# PIC32ETH.net
KiCad netlist of a schematic drawn in Altium Designer
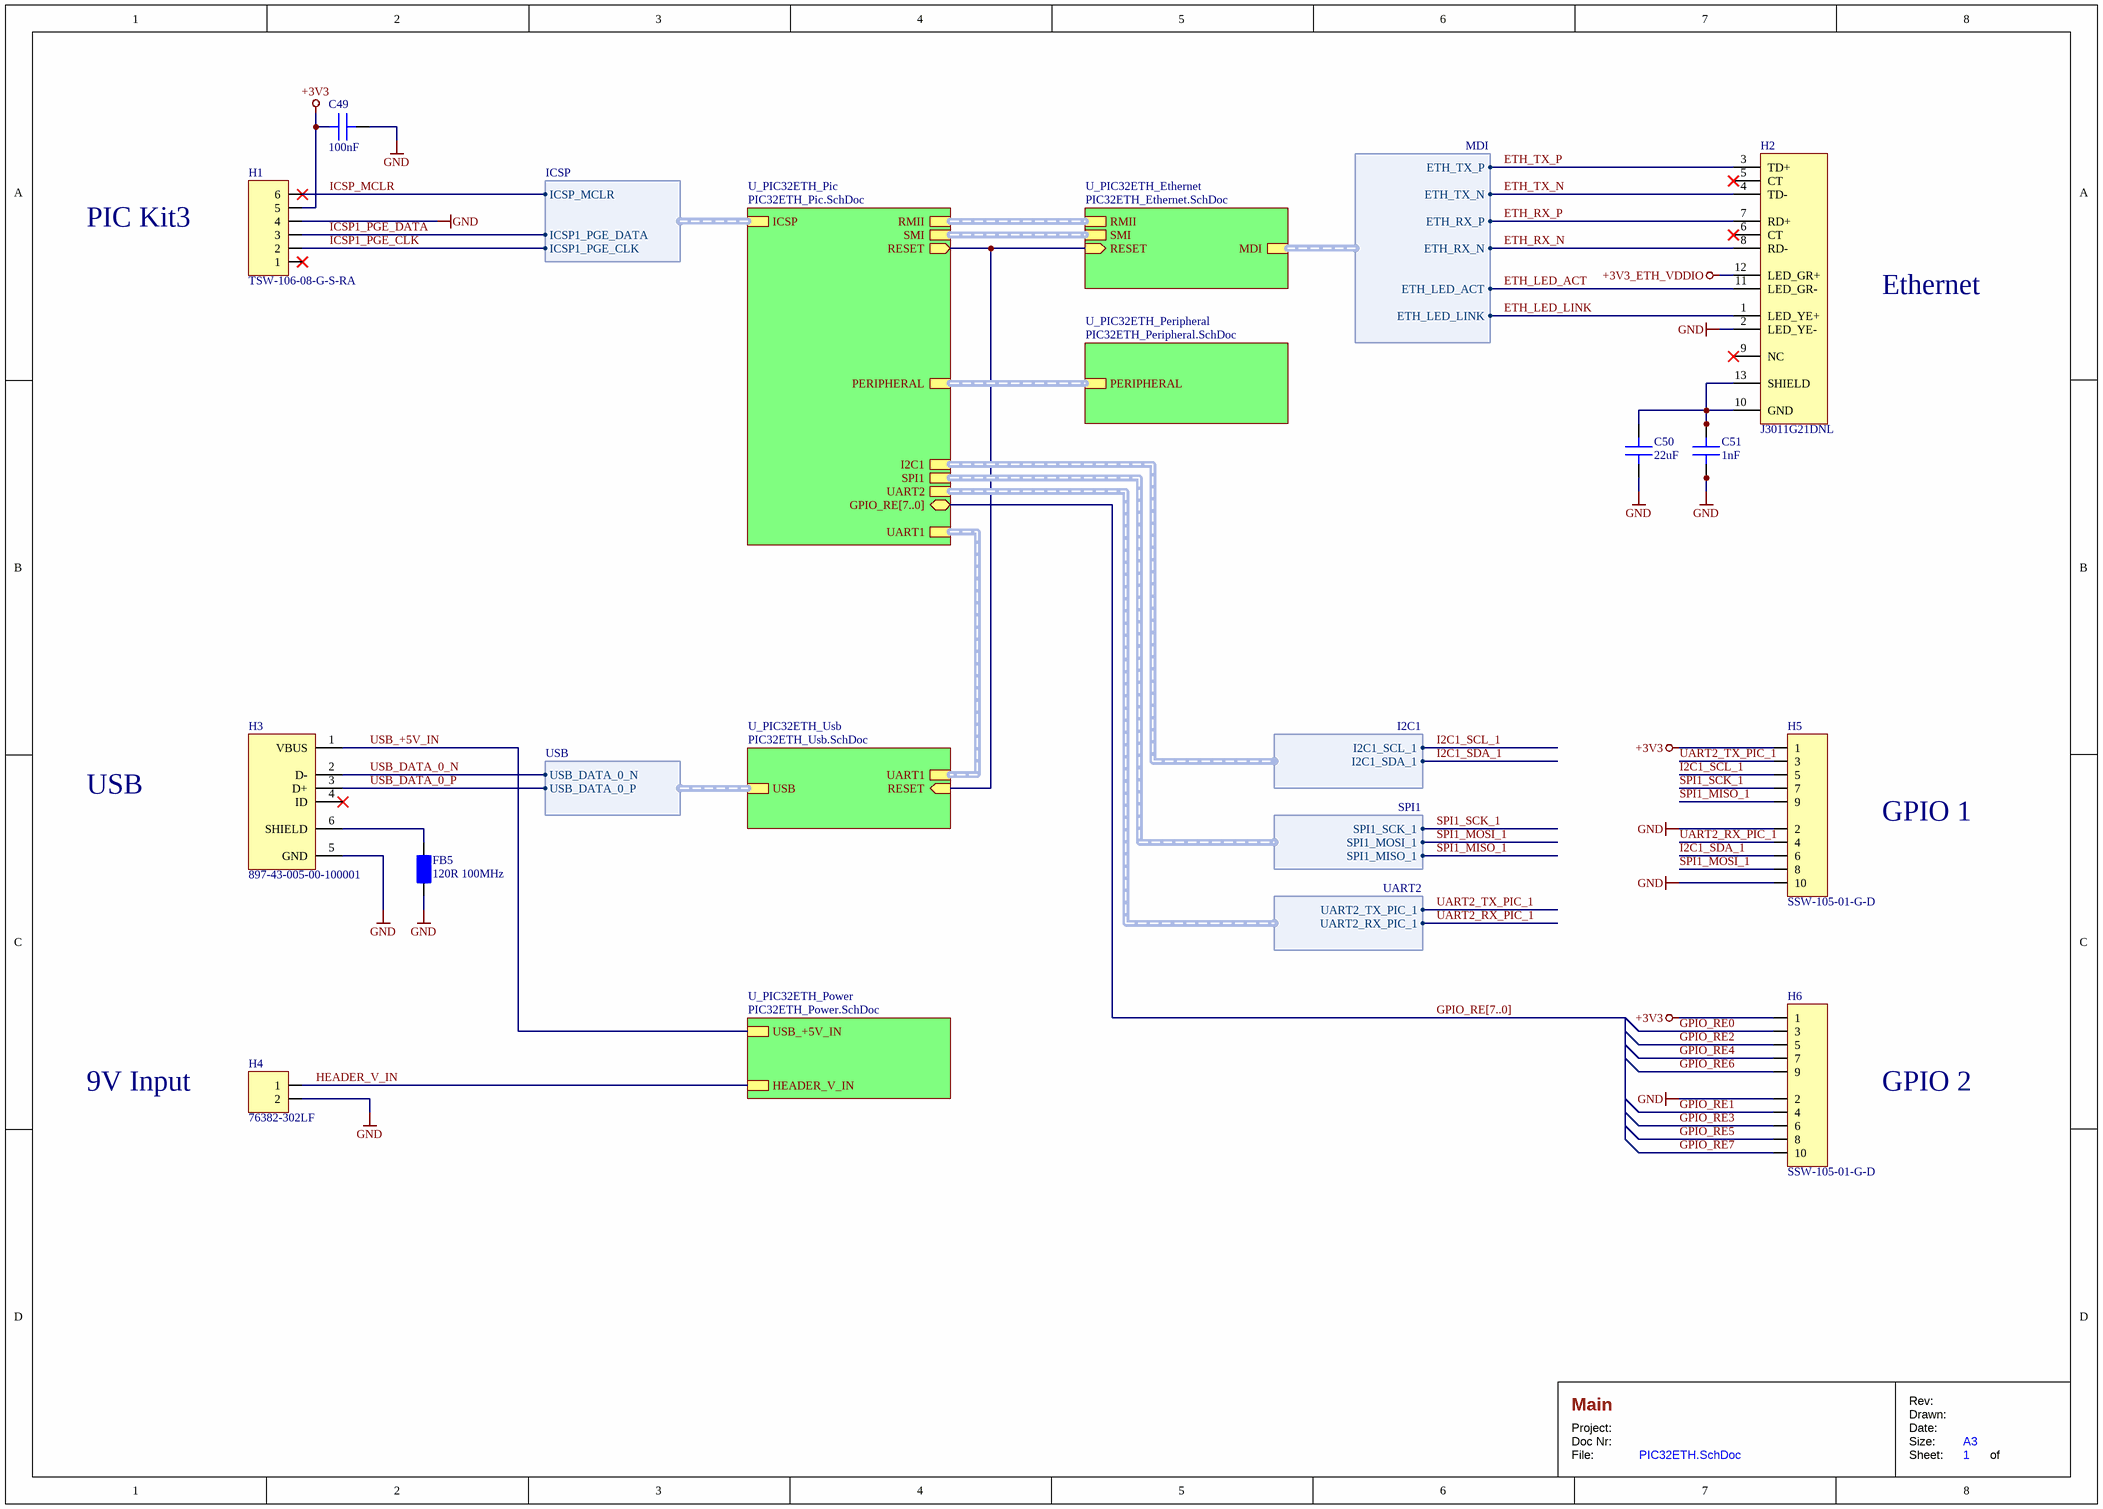
[diagram p0: PIC32ETH.SchDoc]

(export (version "E")
  (design (tool "Eeschema 10.0.6"))
  (components
    (comp (ref "C49")
      (value "100nF")
      (footprint "C_CHIP2012N")
      (description "C CERAMIC 100nF 50V 10% 2012")
      (fields (field (name "MANUFACTURER") "Kemet") (field (name "PART NUMBER") "C0805C104K5RACTU"))
      (libsource (lib "PIC32ETH") (part "C_C0805C104K5RACTU"))
    )
    (comp (ref "C50")
      (value "22uF")
      (footprint "C_CHIP3216N")
      (description "C CERAMIC 22uF 10V 10% 3216")
      (fields (field (name "PART NUMBER") "C1206C226K8RAC7800") (field (name "MANUFACTURER") "Kemet"))
      (libsource (lib "PIC32ETH") (part "C_C1206C226K8RAC7800"))
    )
    (comp (ref "C51")
      (value "1nF")
      (footprint "C_CHIP2012N")
      (description "C CERAMIC 1nF 50V 10% 2012")
      (fields (field (name "MANUFACTURER") "Kemet") (field (name "PART NUMBER") "C0805C102K5RACTU"))
      (libsource (lib "PIC32ETH") (part "C_C0805C102K5RACTU"))
    )
    (comp (ref "FB5")
      (value "120R 100MHz")
      (footprint "FB_CHIP3216N")
      (description "FB 120R 100MHz 6A 3216")
      (fields
        (field (name "MANUFACTURER") "Murata Electronics")
        (field (name "PART NUMBER") "BLM31KN121SN1L")
      )
      (libsource (lib "PIC32ETH") (part "FB_BLM31KN121SN1L"))
    )
    (comp (ref "H1")
      (value "TSW-106-08-G-S-RA")
      (footprint "H_TSW-106-08-G-S-RA")
      (description "H GENERAL HEADER 6POS 1ROW 2.54mm ANGLE THT")
      (fields (field (name "MANUFACTURER") "Samtec Inc.") (field (name "VOLTAGE") "550VAC, 770VDC"))
      (libsource (lib "PIC32ETH") (part "H_TSW-106-08-G-S-RA"))
    )
    (comp (ref "H2")
      (value "J3011G21DNL")
      (footprint "H_J3011G21DNL")
      (description "H RJ45 SOCKET 1PORT ANGLE SMT")
      (fields (field (name "MANUFACTURER") "Pulse") (field (name "VOLTAGE") "n/a"))
      (libsource (lib "PIC32ETH") (part "H_J3011G21DNL"))
    )
    (comp (ref "H3")
      (value "897-43-005-00-100001")
      (footprint "H_897-43-005-00-100001")
      (description "H USB SOCKET 1PORT B-MINI ANGLE SMT")
      (fields (field (name "MANUFACTURER") "Mill-Max Manufacturing Corp.") (field (name "VOLTAGE") "30VAC"))
      (libsource (lib "PIC32ETH") (part "H_897-43-005-00-100001"))
    )
    (comp (ref "H4")
      (value "76382-302LF")
      (footprint "H_76382-302LF")
      (description "H GENERAL HEADER 2POS 1ROW 2.54mm ANGLE THT")
      (fields (field (name "MANUFACTURER") "Amphenol ICC") (field (name "VOLTAGE") "1000V"))
      (libsource (lib "PIC32ETH") (part "H_76382-302LF"))
    )
    (comp (ref "H5")
      (value "SSW-105-01-G-D")
      (footprint "H_SSW-105-01-G-D")
      (description "H GENERAL SOCKET 10POS 2ROW 2.54mm VERTICAL THT")
      (fields (field (name "MANUFACTURER") "Samtec Inc.") (field (name "VOLTAGE") "465VAC, 655VDC"))
      (libsource (lib "PIC32ETH") (part "H_SSW-105-01-G-D"))
    )
    (comp (ref "H6")
      (value "SSW-105-01-G-D")
      (footprint "H_SSW-105-01-G-D")
      (description "H GENERAL SOCKET 10POS 2ROW 2.54mm VERTICAL THT")
      (fields (field (name "MANUFACTURER") "Samtec Inc.") (field (name "VOLTAGE") "465VAC, 655VDC"))
      (libsource (lib "PIC32ETH") (part "H_SSW-105-01-G-D"))
    )
  )
  (nets
    (net (code "7") (name "+3V3") (class "Default")
      (node (ref "C49") (pin "1") (pinfunction "1_1") (pintype "passive"))
      (node (ref "H1") (pin "5") (pinfunction "5_5") (pintype "passive"))
      (node (ref "H5") (pin "1") (pinfunction "1_1") (pintype "passive"))
      (node (ref "H6") (pin "1") (pinfunction "1_1") (pintype "passive"))
    )
    (net (code "8") (name "+3V3_ETH_VDDIO") (class "Default")
      (node (ref "H2") (pin "12") (pinfunction "LED_GR+_12") (pintype "passive"))
    )
    (net (code "9") (name "/ETH_LED_ACT") (class "Default")
      (node (ref "H2") (pin "11") (pinfunction "LED_GR-_11") (pintype "passive"))
    )
    (net (code "10") (name "/ETH_LED_LINK") (class "Default")
      (node (ref "H2") (pin "1") (pinfunction "LED_YE+_1") (pintype "passive"))
    )
    (net (code "11") (name "/ETH_RX_N") (class "Default")
      (node (ref "H2") (pin "8") (pinfunction "RD-_8") (pintype "passive"))
    )
    (net (code "12") (name "/ETH_RX_P") (class "Default")
      (node (ref "H2") (pin "7") (pinfunction "RD+_7") (pintype "passive"))
    )
    (net (code "13") (name "/ETH_TX_N") (class "Default")
      (node (ref "H2") (pin "4") (pinfunction "TD-_4") (pintype "passive"))
    )
    (net (code "14") (name "/ETH_TX_P") (class "Default")
      (node (ref "H2") (pin "3") (pinfunction "TD+_3") (pintype "passive"))
    )
    (net (code "15") (name "/GPIO_RE0") (class "Default")
      (node (ref "H6") (pin "3") (pinfunction "3_3") (pintype "passive"))
    )
    (net (code "16") (name "/GPIO_RE1") (class "Default")
      (node (ref "H6") (pin "4") (pinfunction "4_4") (pintype "passive"))
    )
    (net (code "17") (name "/GPIO_RE2") (class "Default")
      (node (ref "H6") (pin "5") (pinfunction "5_5") (pintype "passive"))
    )
    (net (code "18") (name "/GPIO_RE3") (class "Default")
      (node (ref "H6") (pin "6") (pinfunction "6_6") (pintype "passive"))
    )
    (net (code "19") (name "/GPIO_RE4") (class "Default")
      (node (ref "H6") (pin "7") (pinfunction "7_7") (pintype "passive"))
    )
    (net (code "20") (name "/GPIO_RE5") (class "Default")
      (node (ref "H6") (pin "8") (pinfunction "8_8") (pintype "passive"))
    )
    (net (code "21") (name "/GPIO_RE6") (class "Default")
      (node (ref "H6") (pin "9") (pinfunction "9_9") (pintype "passive"))
    )
    (net (code "22") (name "/GPIO_RE7") (class "Default")
      (node (ref "H6") (pin "10") (pinfunction "10_10") (pintype "passive"))
    )
    (net (code "24") (name "/HEADER_V_IN") (class "Default")
      (node (ref "H4") (pin "1") (pinfunction "1_1") (pintype "passive"))
    )
    (net (code "25") (name "/I2C1_SCL_1") (class "Default")
      (node (ref "H5") (pin "5") (pinfunction "5_5") (pintype "passive"))
    )
    (net (code "26") (name "/I2C1_SDA_1") (class "Default")
      (node (ref "H5") (pin "6") (pinfunction "6_6") (pintype "passive"))
    )
    (net (code "27") (name "/ICSP1_PGE_CLK") (class "Default")
      (node (ref "H1") (pin "2") (pinfunction "2_2") (pintype "passive"))
    )
    (net (code "28") (name "/ICSP1_PGE_DATA") (class "Default")
      (node (ref "H1") (pin "3") (pinfunction "3_3") (pintype "passive"))
    )
    (net (code "29") (name "/ICSP_MCLR") (class "Default")
      (node (ref "H1") (pin "6") (pinfunction "6_6") (pintype "passive+no_connect"))
    )
    (net (code "34") (name "/SPI1_MISO_1") (class "Default")
      (node (ref "H5") (pin "9") (pinfunction "9_9") (pintype "passive"))
    )
    (net (code "35") (name "/SPI1_MOSI_1") (class "Default")
      (node (ref "H5") (pin "8") (pinfunction "8_8") (pintype "passive"))
    )
    (net (code "36") (name "/SPI1_SCK_1") (class "Default")
      (node (ref "H5") (pin "7") (pinfunction "7_7") (pintype "passive"))
    )
    (net (code "38") (name "/UART2_RX_PIC_1") (class "Default")
      (node (ref "H5") (pin "4") (pinfunction "4_4") (pintype "passive"))
    )
    (net (code "39") (name "/UART2_TX_PIC_1") (class "Default")
      (node (ref "H5") (pin "3") (pinfunction "3_3") (pintype "passive"))
    )
    (net (code "40") (name "/USB_+5V_IN") (class "Default")
      (node (ref "H3") (pin "1") (pinfunction "VBUS_1") (pintype "passive"))
    )
    (net (code "41") (name "/USB_DATA_0_N") (class "Default")
      (node (ref "H3") (pin "2") (pinfunction "D-_2") (pintype "passive"))
    )
    (net (code "42") (name "/USB_DATA_0_P") (class "Default")
      (node (ref "H3") (pin "3") (pinfunction "D+_3") (pintype "passive"))
    )
    (net (code "49") (name "GND") (class "Default")
      (node (ref "C49") (pin "2") (pinfunction "2_2") (pintype "passive"))
      (node (ref "C50") (pin "1") (pinfunction "1_1") (pintype "passive"))
      (node (ref "C51") (pin "1") (pinfunction "1_1") (pintype "passive"))
      (node (ref "FB5") (pin "2") (pinfunction "2_2") (pintype "passive"))
      (node (ref "H1") (pin "4") (pinfunction "4_4") (pintype "passive"))
      (node (ref "H2") (pin "2") (pinfunction "LED_YE-_2") (pintype "passive"))
      (node (ref "H3") (pin "5") (pinfunction "GND_5") (pintype "passive"))
      (node (ref "H4") (pin "2") (pinfunction "2_2") (pintype "passive"))
      (node (ref "H5") (pin "10") (pinfunction "10_10") (pintype "passive"))
      (node (ref "H5") (pin "2") (pinfunction "2_2") (pintype "passive"))
      (node (ref "H6") (pin "2") (pinfunction "2_2") (pintype "passive"))
    )
    (net (code "50") (name "Net-(H2-GND)") (class "Default")
      (node (ref "C50") (pin "2") (pinfunction "2_2") (pintype "passive"))
      (node (ref "C51") (pin "2") (pinfunction "2_2") (pintype "passive"))
      (node (ref "H2") (pin "10") (pinfunction "GND_10") (pintype "passive"))
      (node (ref "H2") (pin "13") (pinfunction "SHIELD_13") (pintype "passive"))
    )
    (net (code "51") (name "Net-(H3-SHIELD)") (class "Default")
      (node (ref "FB5") (pin "1") (pinfunction "1_1") (pintype "passive"))
      (node (ref "H3") (pin "6") (pinfunction "SHIELD_6") (pintype "passive"))
    )
    (net (code "52") (name "unconnected-(H1-Pad1)") (class "Default")
      (node (ref "H1") (pin "1") (pinfunction "1_1") (pintype "passive+no_connect"))
    )
    (net (code "53") (name "unconnected-(H2-CT-Pad5)") (class "Default")
      (node (ref "H2") (pin "5") (pinfunction "CT_5") (pintype "passive+no_connect"))
    )
    (net (code "54") (name "unconnected-(H2-CT-Pad6)") (class "Default")
      (node (ref "H2") (pin "6") (pinfunction "CT_6") (pintype "passive+no_connect"))
    )
    (net (code "55") (name "unconnected-(H2-NC-Pad9)") (class "Default")
      (node (ref "H2") (pin "9") (pinfunction "NC_9") (pintype "passive+no_connect"))
    )
    (net (code "56") (name "unconnected-(H3-ID-Pad4)") (class "Default")
      (node (ref "H3") (pin "4") (pinfunction "ID_4") (pintype "passive+no_connect"))
    )
  )
)
